# Voltage_Regulator.net
KiCad netlist of a schematic drawn in Altium Designer
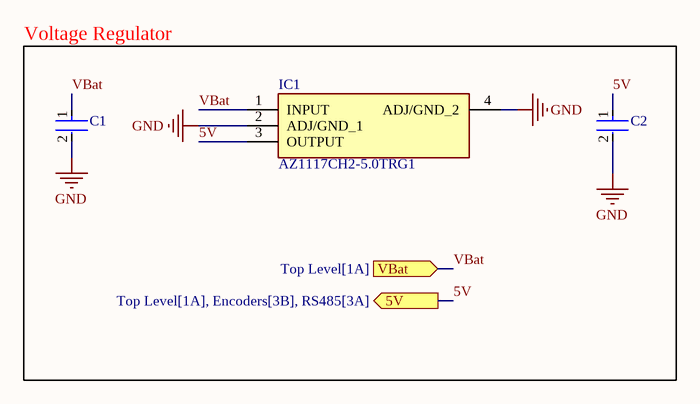
[diagram p0: Voltage Regulator.SchDoc]

(export (version "E")
  (design (tool "Eeschema 10.0.6"))
  (components
    (comp (ref "C1")
      (value "CL31A106MAHNNNE")
      (footprint "FP-CL31-IPC_B")
      (description "Cap Ceramic 10uF 25V X5R ±20% SMD 1206 +85°C Embossed T/R")
      (fields (field (name "TOLERANCE") "20%"))
      (libsource (lib "Altium Content Vault") (part "b4654b650e69147ec39a6b967a45e02"))
    )
    (comp (ref "C2")
      (value "CL31A226MOCLNNC")
      (footprint "FP-CL31-IPC_A")
      (description "Cap Ceramic 22uF 16V X5R ±20% SMD 1206 +85°C Embossed T/R")
      (fields (field (name "TOLERANCE") "20%") (field (name "VOLTAGE") "16V"))
      (libsource (lib "Altium Content Vault") (part "b4654b650e69147ec39a6b967a45e02"))
    )
    (comp (ref "IC1")
      (value "AZ1117CH2-5.0TRG1")
      (footprint "SOT230P700X180-4N")
      (description "Integrated Circuit")
      (fields (field (name "MOUSER PART NUMBER") "621-AZ1117CH2-5.0TRG"))
      (libsource (lib "*") (part "AZ1117CH2-5.0TRG1"))
    )
  )
  (nets
    (net (code "1") (name "/5V") (class "Default")
      (node (ref "C2") (pin "1") (pinfunction "1_1") (pintype "passive"))
      (node (ref "IC1") (pin "3") (pinfunction "OUTPUT_3") (pintype "passive"))
    )
    (net (code "2") (name "/VBat") (class "Default")
      (node (ref "C1") (pin "1") (pinfunction "1_1") (pintype "passive"))
      (node (ref "IC1") (pin "1") (pinfunction "INPUT_1") (pintype "passive"))
    )
    (net (code "3") (name "GND") (class "Default")
      (node (ref "C1") (pin "2") (pinfunction "2_2") (pintype "passive"))
      (node (ref "C2") (pin "2") (pinfunction "2_2") (pintype "passive"))
      (node (ref "IC1") (pin "2") (pinfunction "ADJ/GND_1_2") (pintype "passive"))
      (node (ref "IC1") (pin "4") (pinfunction "ADJ/GND_2_4") (pintype "passive"))
    )
  )
)
